# BUS_TEE_1.net
KiCad netlist of a schematic drawn in EAGLE
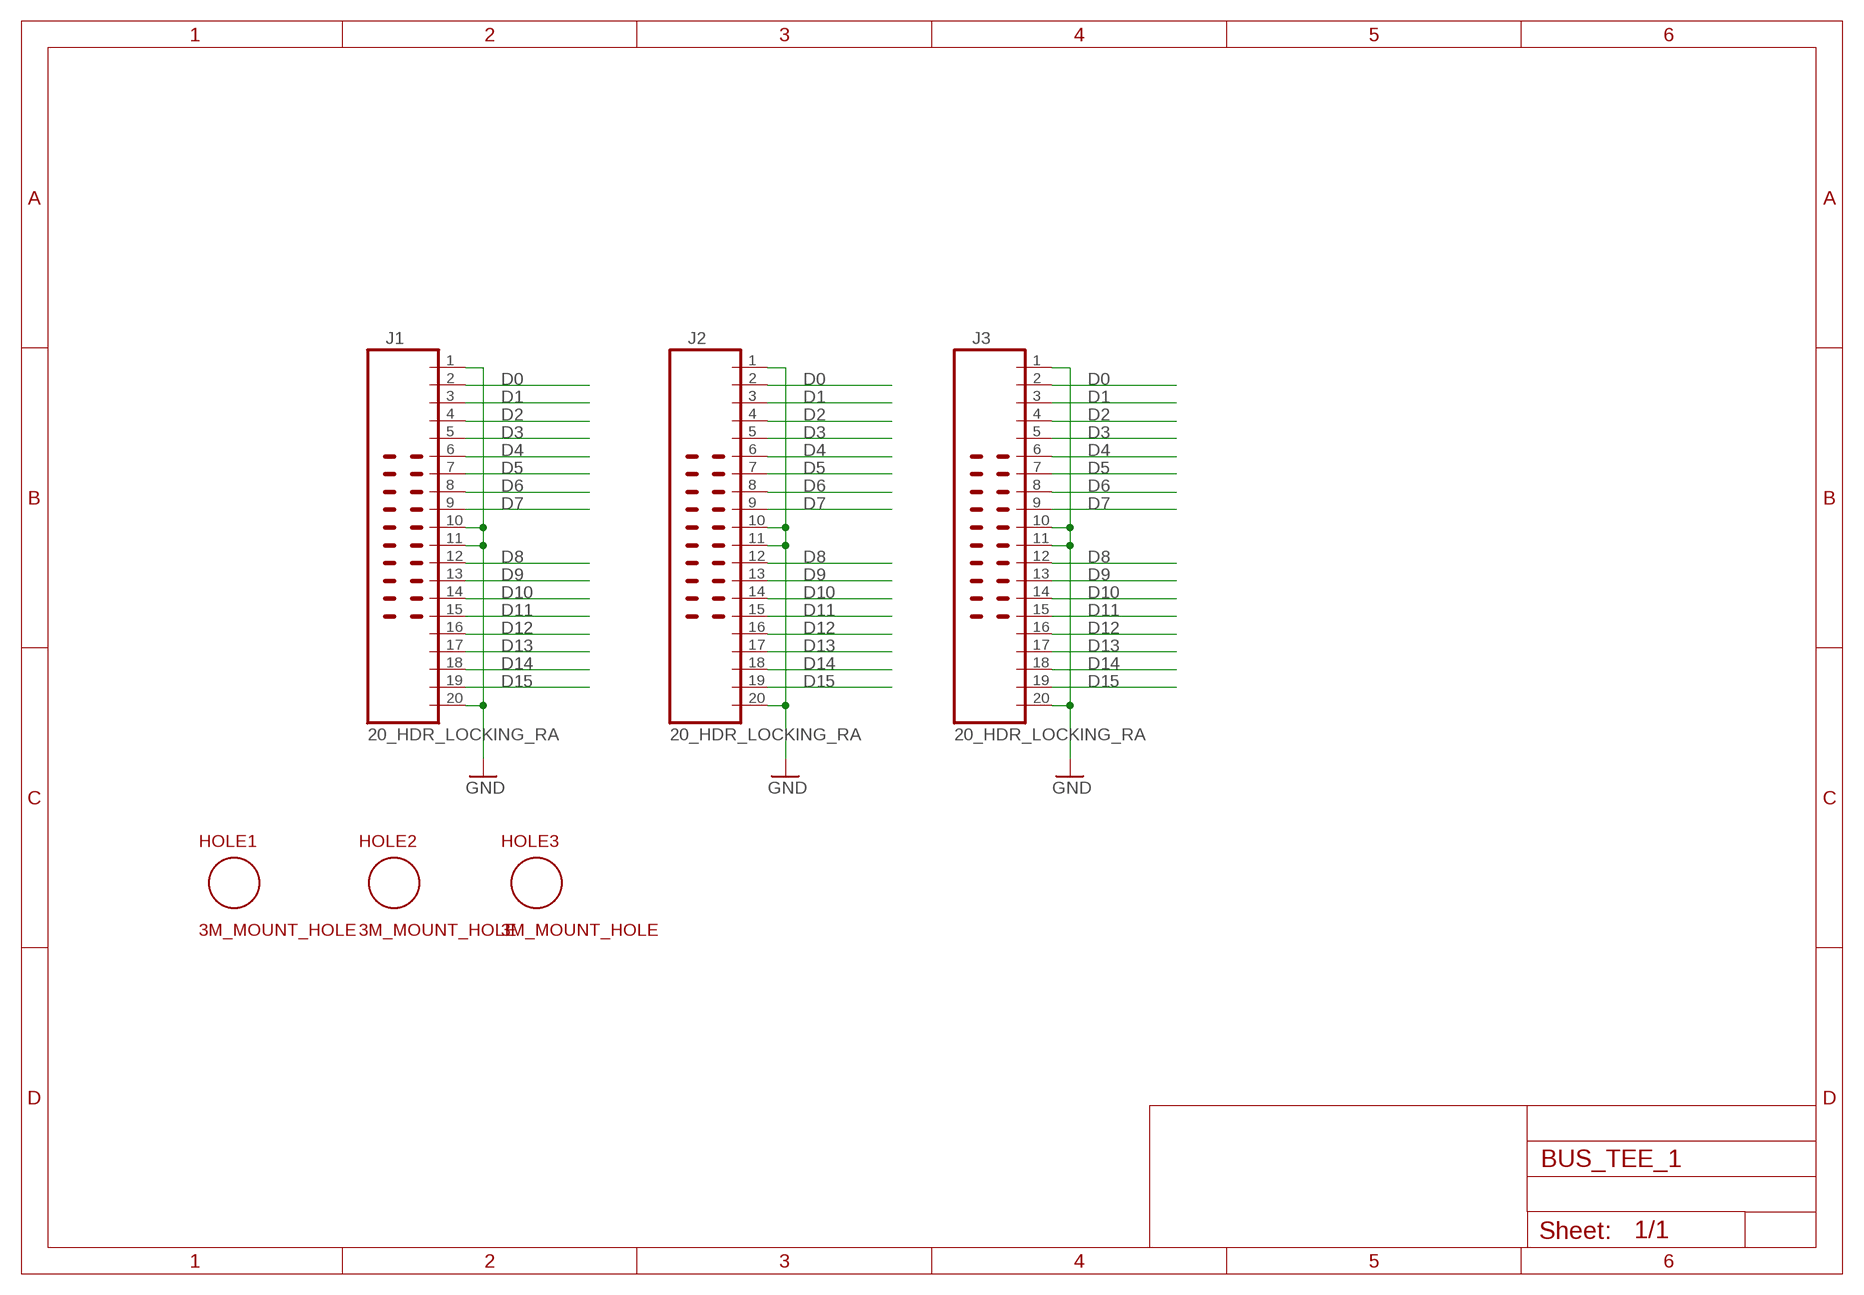
[diagram p0: schematic, sheet 1]

(export (version "E")
  (design (tool "Eeschema 10.0.6"))
  (components
    (comp (ref "HOLE1")
      (value "3M_MOUNT_HOLE")
      (footprint "eagle-import:3M_HOLE")
      (libsource (lib "eagle-import") (part "3M_MOUNT_HOLE"))
    )
    (comp (ref "HOLE2")
      (value "3M_MOUNT_HOLE")
      (footprint "eagle-import:3M_HOLE")
      (libsource (lib "eagle-import") (part "3M_MOUNT_HOLE"))
    )
    (comp (ref "HOLE3")
      (value "3M_MOUNT_HOLE")
      (footprint "eagle-import:3M_HOLE")
      (libsource (lib "eagle-import") (part "3M_MOUNT_HOLE"))
    )
    (comp (ref "J1")
      (value "20_HDR_LOCKING_RA")
      (footprint "eagle-import:20_HDR_LOCKING_RA")
      (libsource (lib "eagle-import") (part "20_HDR_LOCKING_RA"))
    )
    (comp (ref "J2")
      (value "20_HDR_LOCKING_RA")
      (footprint "eagle-import:20_HDR_LOCKING_RA")
      (libsource (lib "eagle-import") (part "20_HDR_LOCKING_RA"))
    )
    (comp (ref "J3")
      (value "20_HDR_LOCKING_RA")
      (footprint "eagle-import:20_HDR_LOCKING_RA")
      (libsource (lib "eagle-import") (part "20_HDR_LOCKING_RA"))
    )
  )
  (nets
    (net (code "1") (name "/D0") (class "Default")
      (node (ref "J1") (pin "2") (pinfunction "2_2") (pintype "bidirectional"))
      (node (ref "J2") (pin "2") (pinfunction "2_2") (pintype "bidirectional"))
      (node (ref "J3") (pin "2") (pinfunction "2_2") (pintype "bidirectional"))
    )
    (net (code "2") (name "/D1") (class "Default")
      (node (ref "J1") (pin "3") (pinfunction "3_3") (pintype "bidirectional"))
      (node (ref "J2") (pin "3") (pinfunction "3_3") (pintype "bidirectional"))
      (node (ref "J3") (pin "3") (pinfunction "3_3") (pintype "bidirectional"))
    )
    (net (code "3") (name "/D2") (class "Default")
      (node (ref "J1") (pin "4") (pinfunction "4_4") (pintype "bidirectional"))
      (node (ref "J2") (pin "4") (pinfunction "4_4") (pintype "bidirectional"))
      (node (ref "J3") (pin "4") (pinfunction "4_4") (pintype "bidirectional"))
    )
    (net (code "4") (name "/D3") (class "Default")
      (node (ref "J1") (pin "5") (pinfunction "5_5") (pintype "bidirectional"))
      (node (ref "J2") (pin "5") (pinfunction "5_5") (pintype "bidirectional"))
      (node (ref "J3") (pin "5") (pinfunction "5_5") (pintype "bidirectional"))
    )
    (net (code "5") (name "/D4") (class "Default")
      (node (ref "J1") (pin "6") (pinfunction "6_6") (pintype "bidirectional"))
      (node (ref "J2") (pin "6") (pinfunction "6_6") (pintype "bidirectional"))
      (node (ref "J3") (pin "6") (pinfunction "6_6") (pintype "bidirectional"))
    )
    (net (code "6") (name "/D5") (class "Default")
      (node (ref "J1") (pin "7") (pinfunction "7_7") (pintype "bidirectional"))
      (node (ref "J2") (pin "7") (pinfunction "7_7") (pintype "bidirectional"))
      (node (ref "J3") (pin "7") (pinfunction "7_7") (pintype "bidirectional"))
    )
    (net (code "7") (name "/D6") (class "Default")
      (node (ref "J1") (pin "8") (pinfunction "8_8") (pintype "bidirectional"))
      (node (ref "J2") (pin "8") (pinfunction "8_8") (pintype "bidirectional"))
      (node (ref "J3") (pin "8") (pinfunction "8_8") (pintype "bidirectional"))
    )
    (net (code "8") (name "/D7") (class "Default")
      (node (ref "J1") (pin "9") (pinfunction "9_9") (pintype "bidirectional"))
      (node (ref "J2") (pin "9") (pinfunction "9_9") (pintype "bidirectional"))
      (node (ref "J3") (pin "9") (pinfunction "9_9") (pintype "bidirectional"))
    )
    (net (code "9") (name "/D8") (class "Default")
      (node (ref "J1") (pin "12") (pinfunction "12_12") (pintype "bidirectional"))
      (node (ref "J2") (pin "12") (pinfunction "12_12") (pintype "bidirectional"))
      (node (ref "J3") (pin "12") (pinfunction "12_12") (pintype "bidirectional"))
    )
    (net (code "10") (name "/D9") (class "Default")
      (node (ref "J1") (pin "13") (pinfunction "13_13") (pintype "bidirectional"))
      (node (ref "J2") (pin "13") (pinfunction "13_13") (pintype "bidirectional"))
      (node (ref "J3") (pin "13") (pinfunction "13_13") (pintype "bidirectional"))
    )
    (net (code "11") (name "/D10") (class "Default")
      (node (ref "J1") (pin "14") (pinfunction "14_14") (pintype "bidirectional"))
      (node (ref "J2") (pin "14") (pinfunction "14_14") (pintype "bidirectional"))
      (node (ref "J3") (pin "14") (pinfunction "14_14") (pintype "bidirectional"))
    )
    (net (code "12") (name "/D11") (class "Default")
      (node (ref "J1") (pin "15") (pinfunction "15_15") (pintype "bidirectional"))
      (node (ref "J2") (pin "15") (pinfunction "15_15") (pintype "bidirectional"))
      (node (ref "J3") (pin "15") (pinfunction "15_15") (pintype "bidirectional"))
    )
    (net (code "13") (name "/D12") (class "Default")
      (node (ref "J1") (pin "16") (pinfunction "16_16") (pintype "bidirectional"))
      (node (ref "J2") (pin "16") (pinfunction "16_16") (pintype "bidirectional"))
      (node (ref "J3") (pin "16") (pinfunction "16_16") (pintype "bidirectional"))
    )
    (net (code "14") (name "/D13") (class "Default")
      (node (ref "J1") (pin "17") (pinfunction "17_17") (pintype "bidirectional"))
      (node (ref "J2") (pin "17") (pinfunction "17_17") (pintype "bidirectional"))
      (node (ref "J3") (pin "17") (pinfunction "17_17") (pintype "bidirectional"))
    )
    (net (code "15") (name "/D14") (class "Default")
      (node (ref "J1") (pin "18") (pinfunction "18_18") (pintype "bidirectional"))
      (node (ref "J2") (pin "18") (pinfunction "18_18") (pintype "bidirectional"))
      (node (ref "J3") (pin "18") (pinfunction "18_18") (pintype "bidirectional"))
    )
    (net (code "16") (name "/D15") (class "Default")
      (node (ref "J1") (pin "19") (pinfunction "19_19") (pintype "bidirectional"))
      (node (ref "J2") (pin "19") (pinfunction "19_19") (pintype "bidirectional"))
      (node (ref "J3") (pin "19") (pinfunction "19_19") (pintype "bidirectional"))
    )
    (net (code "17") (name "GND") (class "Default")
      (node (ref "J1") (pin "1") (pinfunction "1_1") (pintype "bidirectional"))
      (node (ref "J1") (pin "10") (pinfunction "10_10") (pintype "bidirectional"))
      (node (ref "J1") (pin "11") (pinfunction "11_11") (pintype "bidirectional"))
      (node (ref "J1") (pin "20") (pinfunction "20_20") (pintype "bidirectional"))
      (node (ref "J2") (pin "1") (pinfunction "1_1") (pintype "bidirectional"))
      (node (ref "J2") (pin "10") (pinfunction "10_10") (pintype "bidirectional"))
      (node (ref "J2") (pin "11") (pinfunction "11_11") (pintype "bidirectional"))
      (node (ref "J2") (pin "20") (pinfunction "20_20") (pintype "bidirectional"))
      (node (ref "J3") (pin "1") (pinfunction "1_1") (pintype "bidirectional"))
      (node (ref "J3") (pin "10") (pinfunction "10_10") (pintype "bidirectional"))
      (node (ref "J3") (pin "11") (pinfunction "11_11") (pintype "bidirectional"))
      (node (ref "J3") (pin "20") (pinfunction "20_20") (pintype "bidirectional"))
    )
  )
)
